# clock.net
KiCad netlist of a schematic drawn in EAGLE
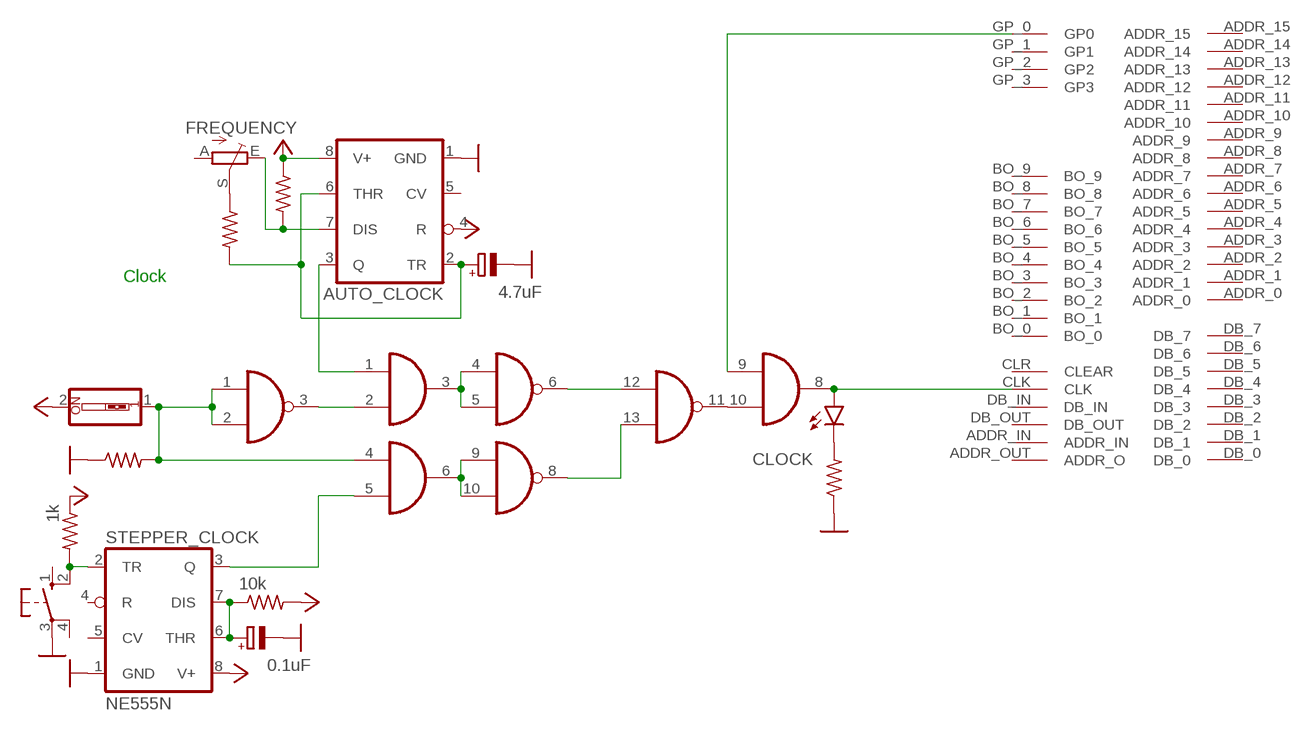
[diagram p0: schematic, sheet 1]

(export (version "E")
  (design (tool "Eeschema 10.0.6"))
  (components
    (comp (ref "AND_GATE_")
      (value "74LS08N")
      (footprint "eagle-import:DIL14")
      (libsource (lib "eagle-import") (part "7408NLS"))
    )
    (comp (ref "AUTO_CLOCK")
      (value "NE555N")
      (footprint "eagle-import:DIL08")
      (libsource (lib "eagle-import") (part "555NNE"))
    )
    (comp (ref "C1")
      (value "4.7uF")
      (footprint "eagle-import:E2-5")
      (libsource (lib "eagle-import") (part "CPOL-EUE2-5"))
    )
    (comp (ref "C2")
      (value "0.1uF")
      (footprint "eagle-import:E2-5")
      (libsource (lib "eagle-import") (part "CPOL-EUE2-5"))
    )
    (comp (ref "CLK_MODE")
      (value "SWITCH")
      (footprint "eagle-import:EDG-01")
      (libsource (lib "eagle-import") (part "SW_DIP-1"))
    )
    (comp (ref "CLK_TRIGGER")
      (value "SWITCH")
      (footprint "eagle-import:B3F-10XX")
      (fields (field (name "MPN") "B3F-1000"))
      (libsource (lib "eagle-import") (part "10-XX"))
    )
    (comp (ref "CLOCK")
      (value "Yellow")
      (footprint "eagle-import:LED5MM")
      (libsource (lib "eagle-import") (part "LED5MM"))
    )
    (comp (ref "FREQUENCY")
      (value "100k")
      (footprint "eagle-import:RJ9W")
      (libsource (lib "eagle-import") (part "TRIM_EU-RJ9W"))
    )
    (comp (ref "NAND")
      (value "74ACT00N")
      (footprint "eagle-import:DIL14")
      (libsource (lib "eagle-import") (part "7400NACT"))
    )
    (comp (ref "R1")
      (value "1k")
      (footprint "eagle-import:0204_7")
      (libsource (lib "eagle-import") (part "R-US_0204/7"))
    )
    (comp (ref "R2")
      (value "1k")
      (footprint "eagle-import:0204_7")
      (libsource (lib "eagle-import") (part "R-US_0204/7"))
    )
    (comp (ref "R3")
      (value "10k")
      (footprint "eagle-import:0204_7")
      (libsource (lib "eagle-import") (part "R-US_0204/7"))
    )
    (comp (ref "R4")
      (value "220")
      (footprint "eagle-import:0204_7")
      (libsource (lib "eagle-import") (part "R-US_0204/7"))
    )
    (comp (ref "R5")
      (value "~220")
      (footprint "eagle-import:0204_7")
      (libsource (lib "eagle-import") (part "R-US_0204/7"))
    )
    (comp (ref "R6")
      (value "220")
      (footprint "eagle-import:0204_7")
      (libsource (lib "eagle-import") (part "R-US_0204/7"))
    )
    (comp (ref "STEPPER_CLOCK")
      (value "NE555N")
      (footprint "eagle-import:DIL08")
      (libsource (lib "eagle-import") (part "555NNE"))
    )
    (comp (ref "U$1")
      (value "BACKPLATE_INTERFACEEDGE_FINGER")
      (footprint "eagle-import:BACK_INTERFACE-FOOT")
      (libsource (lib "eagle-import") (part "BACKPLATE_INTERFACEEDGE_FINGER"))
    )
  )
  (nets
    (net (code "1") (name "GND") (class "Default")
      (node (ref "AUTO_CLOCK") (pin "1") (pinfunction "GND_1") (pintype "power_in"))
      (node (ref "C1") (pin "-") (pinfunction "-_-") (pintype "passive"))
      (node (ref "C2") (pin "-") (pinfunction "-_-") (pintype "passive"))
      (node (ref "CLK_TRIGGER") (pin "3") (pinfunction "P_3") (pintype "passive"))
      (node (ref "R4") (pin "1") (pinfunction "1_1") (pintype "passive"))
      (node (ref "R5") (pin "1") (pinfunction "1_1") (pintype "passive"))
      (node (ref "STEPPER_CLOCK") (pin "1") (pinfunction "GND_1") (pintype "power_in"))
    )
    (net (code "2") (name "Net-(AND_GATE_A-I0)") (class "Default")
      (node (ref "AND_GATE_") (pin "1") (pinfunction "I0_1") (pintype "input"))
      (node (ref "AUTO_CLOCK") (pin "3") (pinfunction "Q_3") (pintype "output"))
    )
    (net (code "3") (name "Net-(AND_GATE_A-I1)") (class "Default")
      (node (ref "AND_GATE_") (pin "2") (pinfunction "I1_2") (pintype "input"))
      (node (ref "NAND") (pin "3") (pinfunction "O_3") (pintype "output"))
    )
    (net (code "4") (name "Net-(AND_GATE_A-O)") (class "Default")
      (node (ref "AND_GATE_") (pin "3") (pinfunction "O_3") (pintype "output"))
      (node (ref "NAND") (pin "4") (pinfunction "I0_4") (pintype "input"))
      (node (ref "NAND") (pin "5") (pinfunction "I1_5") (pintype "input"))
    )
    (net (code "5") (name "Net-(AND_GATE_B-I0)") (class "Default")
      (node (ref "AND_GATE_") (pin "4") (pinfunction "I0_4") (pintype "input"))
      (node (ref "CLK_MODE") (pin "1") (pinfunction "1_1") (pintype "passive"))
      (node (ref "NAND") (pin "1") (pinfunction "I0_1") (pintype "input"))
      (node (ref "NAND") (pin "2") (pinfunction "I1_2") (pintype "input"))
      (node (ref "R4") (pin "2") (pinfunction "2_2") (pintype "passive"))
    )
    (net (code "6") (name "Net-(AND_GATE_B-I1)") (class "Default")
      (node (ref "AND_GATE_") (pin "5") (pinfunction "I1_5") (pintype "input"))
      (node (ref "STEPPER_CLOCK") (pin "3") (pinfunction "Q_3") (pintype "output"))
    )
    (net (code "7") (name "Net-(AND_GATE_B-O)") (class "Default")
      (node (ref "AND_GATE_") (pin "6") (pinfunction "O_6") (pintype "output"))
      (node (ref "NAND") (pin "10") (pinfunction "I1_10") (pintype "input"))
      (node (ref "NAND") (pin "9") (pinfunction "I0_9") (pintype "input"))
    )
    (net (code "8") (name "Net-(AND_GATE_C-I0)") (class "Default")
      (node (ref "AND_GATE_") (pin "9") (pinfunction "I0_9") (pintype "input"))
      (node (ref "U$1") (pin "GP_0") (pinfunction "GP0_GP_0") (pintype "bidirectional"))
    )
    (net (code "9") (name "Net-(AND_GATE_C-I1)") (class "Default")
      (node (ref "AND_GATE_") (pin "10") (pinfunction "I1_10") (pintype "input"))
      (node (ref "NAND") (pin "11") (pinfunction "O_11") (pintype "output"))
    )
    (net (code "10") (name "Net-(AND_GATE_C-O)") (class "Default")
      (node (ref "AND_GATE_") (pin "8") (pinfunction "O_8") (pintype "output"))
      (node (ref "CLOCK") (pin "A") (pinfunction "A_A") (pintype "passive"))
      (node (ref "U$1") (pin "CLK") (pinfunction "CLK_CLK") (pintype "bidirectional"))
    )
    (net (code "11") (name "Net-(AUTO_CLOCK-DIS)") (class "Default")
      (node (ref "AUTO_CLOCK") (pin "7") (pinfunction "DIS_7") (pintype "input"))
      (node (ref "FREQUENCY") (pin "E") (pinfunction "E_E") (pintype "passive"))
      (node (ref "R1") (pin "2") (pinfunction "2_2") (pintype "passive"))
    )
    (net (code "12") (name "Net-(AUTO_CLOCK-THR)") (class "Default")
      (node (ref "AUTO_CLOCK") (pin "2") (pinfunction "TR_2") (pintype "input"))
      (node (ref "AUTO_CLOCK") (pin "6") (pinfunction "THR_6") (pintype "input"))
      (node (ref "C1") (pin "+") (pinfunction "+_+") (pintype "passive"))
      (node (ref "R6") (pin "2") (pinfunction "2_2") (pintype "passive"))
    )
    (net (code "13") (name "Net-(CLK_TRIGGER-S1)") (class "Default")
      (node (ref "CLK_TRIGGER") (pin "2") (pinfunction "S1_2") (pintype "passive"))
      (node (ref "R2") (pin "2") (pinfunction "2_2") (pintype "passive"))
      (node (ref "STEPPER_CLOCK") (pin "2") (pinfunction "TR_2") (pintype "input"))
    )
    (net (code "14") (name "Net-(CLOCK-C)") (class "Default")
      (node (ref "CLOCK") (pin "K") (pinfunction "C_K") (pintype "passive"))
      (node (ref "R5") (pin "2") (pinfunction "2_2") (pintype "passive"))
    )
    (net (code "15") (name "Net-(FREQUENCY-PadS)") (class "Default")
      (node (ref "FREQUENCY") (pin "S") (pinfunction "S_S") (pintype "passive"))
      (node (ref "R6") (pin "1") (pinfunction "1_1") (pintype "passive"))
    )
    (net (code "16") (name "Net-(NANDB-O)") (class "Default")
      (node (ref "NAND") (pin "12") (pinfunction "I0_12") (pintype "input"))
      (node (ref "NAND") (pin "6") (pinfunction "O_6") (pintype "output"))
    )
    (net (code "17") (name "Net-(NANDC-O)") (class "Default")
      (node (ref "NAND") (pin "13") (pinfunction "I1_13") (pintype "input"))
      (node (ref "NAND") (pin "8") (pinfunction "O_8") (pintype "output"))
    )
    (net (code "18") (name "Net-(STEPPER_CLOCK-DIS)") (class "Default")
      (node (ref "C2") (pin "+") (pinfunction "+_+") (pintype "passive"))
      (node (ref "R3") (pin "1") (pinfunction "1_1") (pintype "passive"))
      (node (ref "STEPPER_CLOCK") (pin "6") (pinfunction "THR_6") (pintype "input"))
      (node (ref "STEPPER_CLOCK") (pin "7") (pinfunction "DIS_7") (pintype "input"))
    )
    (net (code "19") (name "VCC") (class "Default")
      (node (ref "AUTO_CLOCK") (pin "4") (pinfunction "R_4") (pintype "input"))
      (node (ref "AUTO_CLOCK") (pin "8") (pinfunction "V+_8") (pintype "power_in"))
      (node (ref "CLK_MODE") (pin "2") (pinfunction "2_2") (pintype "passive"))
      (node (ref "R1") (pin "1") (pinfunction "1_1") (pintype "passive"))
      (node (ref "R2") (pin "1") (pinfunction "1_1") (pintype "passive"))
      (node (ref "R3") (pin "2") (pinfunction "2_2") (pintype "passive"))
      (node (ref "STEPPER_CLOCK") (pin "8") (pinfunction "V+_8") (pintype "power_in"))
    )
    (net (code "20") (name "unconnected-(AUTO_CLOCK-CV-Pad5)") (class "Default")
      (node (ref "AUTO_CLOCK") (pin "5") (pinfunction "CV_5") (pintype "input"))
    )
    (net (code "21") (name "unconnected-(CLK_TRIGGER-P1-Pad4)") (class "Default")
      (node (ref "CLK_TRIGGER") (pin "4") (pinfunction "P1_4") (pintype "passive"))
    )
    (net (code "22") (name "unconnected-(CLK_TRIGGER-S-Pad1)") (class "Default")
      (node (ref "CLK_TRIGGER") (pin "1") (pinfunction "S_1") (pintype "passive"))
    )
    (net (code "23") (name "unconnected-(FREQUENCY-PadA)") (class "Default")
      (node (ref "FREQUENCY") (pin "A") (pinfunction "A_A") (pintype "passive"))
    )
    (net (code "24") (name "unconnected-(STEPPER_CLOCK-CV-Pad5)") (class "Default")
      (node (ref "STEPPER_CLOCK") (pin "5") (pinfunction "CV_5") (pintype "input"))
    )
    (net (code "25") (name "unconnected-(STEPPER_CLOCK-R-Pad4)") (class "Default")
      (node (ref "STEPPER_CLOCK") (pin "4") (pinfunction "R_4") (pintype "input"))
    )
    (net (code "26") (name "unconnected-(U$1-PadADDR_0)") (class "Default")
      (node (ref "U$1") (pin "ADDR_0") (pinfunction "ADDR_0_ADDR_0") (pintype "bidirectional"))
    )
    (net (code "27") (name "unconnected-(U$1-PadADDR_1)") (class "Default")
      (node (ref "U$1") (pin "ADDR_1") (pinfunction "ADDR_1_ADDR_1") (pintype "bidirectional"))
    )
    (net (code "28") (name "unconnected-(U$1-PadADDR_2)") (class "Default")
      (node (ref "U$1") (pin "ADDR_2") (pinfunction "ADDR_2_ADDR_2") (pintype "bidirectional"))
    )
    (net (code "29") (name "unconnected-(U$1-PadADDR_3)") (class "Default")
      (node (ref "U$1") (pin "ADDR_3") (pinfunction "ADDR_3_ADDR_3") (pintype "bidirectional"))
    )
    (net (code "30") (name "unconnected-(U$1-PadADDR_4)") (class "Default")
      (node (ref "U$1") (pin "ADDR_4") (pinfunction "ADDR_4_ADDR_4") (pintype "bidirectional"))
    )
    (net (code "31") (name "unconnected-(U$1-PadADDR_5)") (class "Default")
      (node (ref "U$1") (pin "ADDR_5") (pinfunction "ADDR_5_ADDR_5") (pintype "bidirectional"))
    )
    (net (code "32") (name "unconnected-(U$1-PadADDR_6)") (class "Default")
      (node (ref "U$1") (pin "ADDR_6") (pinfunction "ADDR_6_ADDR_6") (pintype "bidirectional"))
    )
    (net (code "33") (name "unconnected-(U$1-PadADDR_7)") (class "Default")
      (node (ref "U$1") (pin "ADDR_7") (pinfunction "ADDR_7_ADDR_7") (pintype "bidirectional"))
    )
    (net (code "34") (name "unconnected-(U$1-PadADDR_8)") (class "Default")
      (node (ref "U$1") (pin "ADDR_8") (pinfunction "ADDR_8_ADDR_8") (pintype "bidirectional"))
    )
    (net (code "35") (name "unconnected-(U$1-PadADDR_9)") (class "Default")
      (node (ref "U$1") (pin "ADDR_9") (pinfunction "ADDR_9_ADDR_9") (pintype "bidirectional"))
    )
    (net (code "36") (name "unconnected-(U$1-PadADDR_10)") (class "Default")
      (node (ref "U$1") (pin "ADDR_10") (pinfunction "ADDR_10_ADDR_10") (pintype "bidirectional"))
    )
    (net (code "37") (name "unconnected-(U$1-PadADDR_11)") (class "Default")
      (node (ref "U$1") (pin "ADDR_11") (pinfunction "ADDR_11_ADDR_11") (pintype "bidirectional"))
    )
    (net (code "38") (name "unconnected-(U$1-PadADDR_12)") (class "Default")
      (node (ref "U$1") (pin "ADDR_12") (pinfunction "ADDR_12_ADDR_12") (pintype "bidirectional"))
    )
    (net (code "39") (name "unconnected-(U$1-PadADDR_13)") (class "Default")
      (node (ref "U$1") (pin "ADDR_13") (pinfunction "ADDR_13_ADDR_13") (pintype "bidirectional"))
    )
    (net (code "40") (name "unconnected-(U$1-PadADDR_14)") (class "Default")
      (node (ref "U$1") (pin "ADDR_14") (pinfunction "ADDR_14_ADDR_14") (pintype "bidirectional"))
    )
    (net (code "41") (name "unconnected-(U$1-PadADDR_15)") (class "Default")
      (node (ref "U$1") (pin "ADDR_15") (pinfunction "ADDR_15_ADDR_15") (pintype "bidirectional"))
    )
    (net (code "42") (name "unconnected-(U$1-PadADDR_IN)") (class "Default")
      (node (ref "U$1") (pin "ADDR_IN") (pinfunction "ADDR_IN_ADDR_IN") (pintype "bidirectional"))
    )
    (net (code "43") (name "unconnected-(U$1-PadBO_0)") (class "Default")
      (node (ref "U$1") (pin "BO_0") (pinfunction "BO_0_BO_0") (pintype "bidirectional"))
    )
    (net (code "44") (name "unconnected-(U$1-PadBO_1)") (class "Default")
      (node (ref "U$1") (pin "BO_1") (pinfunction "BO_1_BO_1") (pintype "bidirectional"))
    )
    (net (code "45") (name "unconnected-(U$1-PadBO_2)") (class "Default")
      (node (ref "U$1") (pin "BO_2") (pinfunction "BO_2_BO_2") (pintype "bidirectional"))
    )
    (net (code "46") (name "unconnected-(U$1-PadBO_3)") (class "Default")
      (node (ref "U$1") (pin "BO_3") (pinfunction "BO_3_BO_3") (pintype "bidirectional"))
    )
    (net (code "47") (name "unconnected-(U$1-PadBO_4)") (class "Default")
      (node (ref "U$1") (pin "BO_4") (pinfunction "BO_4_BO_4") (pintype "bidirectional"))
    )
    (net (code "48") (name "unconnected-(U$1-PadBO_5)") (class "Default")
      (node (ref "U$1") (pin "BO_5") (pinfunction "BO_5_BO_5") (pintype "bidirectional"))
    )
    (net (code "49") (name "unconnected-(U$1-PadBO_6)") (class "Default")
      (node (ref "U$1") (pin "BO_6") (pinfunction "BO_6_BO_6") (pintype "bidirectional"))
    )
    (net (code "50") (name "unconnected-(U$1-PadBO_7)") (class "Default")
      (node (ref "U$1") (pin "BO_7") (pinfunction "BO_7_BO_7") (pintype "bidirectional"))
    )
    (net (code "51") (name "unconnected-(U$1-PadBO_8)") (class "Default")
      (node (ref "U$1") (pin "BO_8") (pinfunction "BO_8_BO_8") (pintype "bidirectional"))
    )
    (net (code "52") (name "unconnected-(U$1-PadBO_9)") (class "Default")
      (node (ref "U$1") (pin "BO_9") (pinfunction "BO_9_BO_9") (pintype "bidirectional"))
    )
    (net (code "53") (name "unconnected-(U$1-PadDB_0)") (class "Default")
      (node (ref "U$1") (pin "DB_0") (pinfunction "DB_0_DB_0") (pintype "bidirectional"))
    )
    (net (code "54") (name "unconnected-(U$1-PadDB_1)") (class "Default")
      (node (ref "U$1") (pin "DB_1") (pinfunction "DB_1_DB_1") (pintype "bidirectional"))
    )
    (net (code "55") (name "unconnected-(U$1-PadDB_2)") (class "Default")
      (node (ref "U$1") (pin "DB_2") (pinfunction "DB_2_DB_2") (pintype "bidirectional"))
    )
    (net (code "56") (name "unconnected-(U$1-PadDB_3)") (class "Default")
      (node (ref "U$1") (pin "DB_3") (pinfunction "DB_3_DB_3") (pintype "bidirectional"))
    )
    (net (code "57") (name "unconnected-(U$1-PadDB_4)") (class "Default")
      (node (ref "U$1") (pin "DB_4") (pinfunction "DB_4_DB_4") (pintype "bidirectional"))
    )
    (net (code "58") (name "unconnected-(U$1-PadDB_5)") (class "Default")
      (node (ref "U$1") (pin "DB_5") (pinfunction "DB_5_DB_5") (pintype "bidirectional"))
    )
    (net (code "59") (name "unconnected-(U$1-PadDB_6)") (class "Default")
      (node (ref "U$1") (pin "DB_6") (pinfunction "DB_6_DB_6") (pintype "bidirectional"))
    )
    (net (code "60") (name "unconnected-(U$1-PadDB_7)") (class "Default")
      (node (ref "U$1") (pin "DB_7") (pinfunction "DB_7_DB_7") (pintype "bidirectional"))
    )
    (net (code "61") (name "unconnected-(U$1-PadDB_IN)") (class "Default")
      (node (ref "U$1") (pin "DB_IN") (pinfunction "DB_IN_DB_IN") (pintype "bidirectional"))
    )
    (net (code "62") (name "unconnected-(U$1-PadDB_OUT)") (class "Default")
      (node (ref "U$1") (pin "DB_OUT") (pinfunction "DB_OUT_DB_OUT") (pintype "bidirectional"))
    )
    (net (code "63") (name "unconnected-(U$1A-ADDR_O-PadADDR_OUT)") (class "Default")
      (node (ref "U$1") (pin "ADDR_OUT") (pinfunction "ADDR_O_ADDR_OUT") (pintype "bidirectional"))
    )
    (net (code "64") (name "unconnected-(U$1A-CLEAR-PadCLR)") (class "Default")
      (node (ref "U$1") (pin "CLR") (pinfunction "CLEAR_CLR") (pintype "bidirectional"))
    )
    (net (code "65") (name "unconnected-(U$1A-GP1-PadGP_1)") (class "Default")
      (node (ref "U$1") (pin "GP_1") (pinfunction "GP1_GP_1") (pintype "bidirectional"))
    )
    (net (code "66") (name "unconnected-(U$1A-GP2-PadGP_2)") (class "Default")
      (node (ref "U$1") (pin "GP_2") (pinfunction "GP2_GP_2") (pintype "bidirectional"))
    )
    (net (code "67") (name "unconnected-(U$1A-GP3-PadGP_3)") (class "Default")
      (node (ref "U$1") (pin "GP_3") (pinfunction "GP3_GP_3") (pintype "bidirectional"))
    )
  )
)
